# Controller.net
KiCad netlist of a schematic drawn in Altium Designer
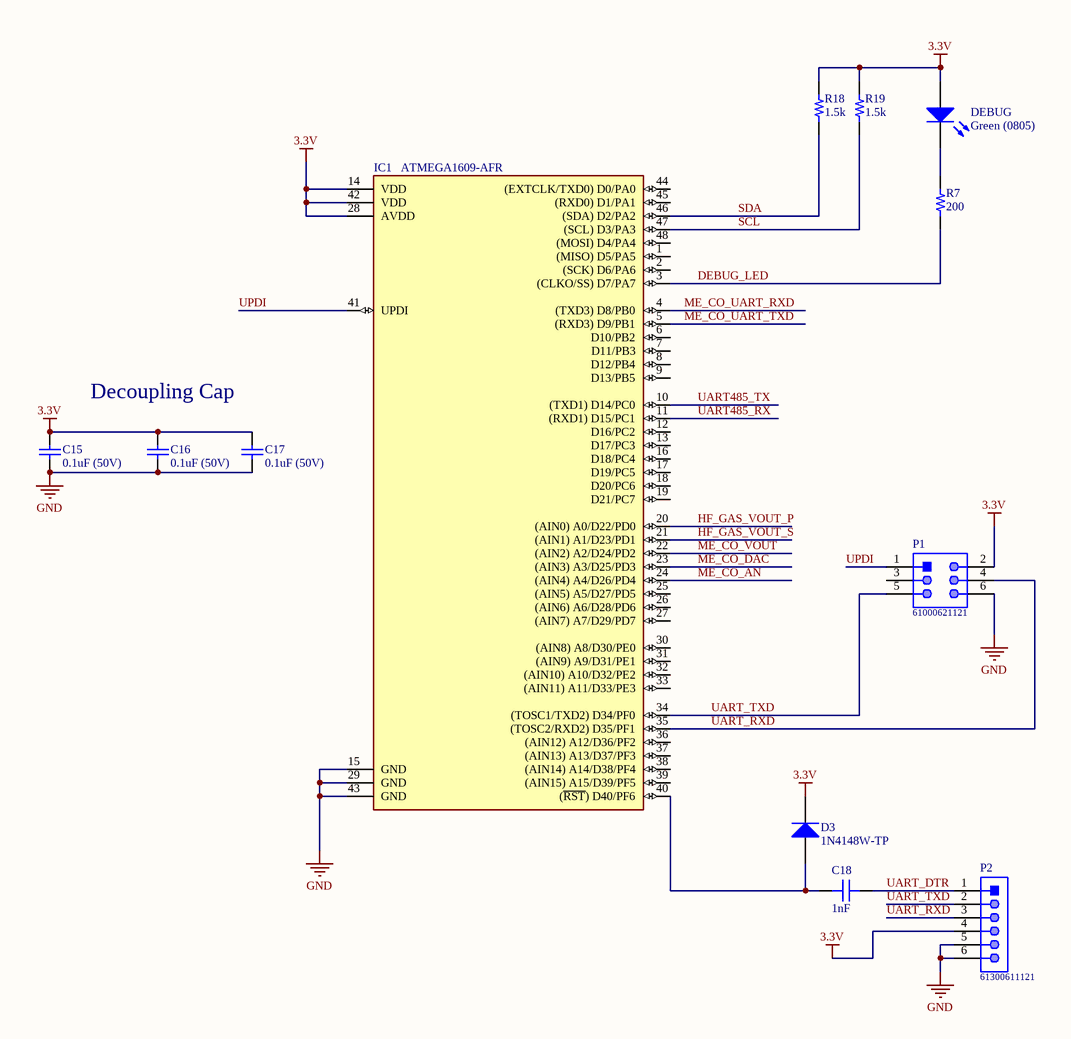
[diagram p0: Controller.SchDoc]

(export (version "E")
  (design (tool "Eeschema 10.0.6"))
  (components
    (comp (ref "C15")
      (value "0.1uF (50V)")
      (footprint "CAPC1608X95X40NL15T15")
      (fields (field (name "PART NUMBER") "VJ0603Y332JXACW1BC") (field (name "MANUFACTURER") "Vitramon"))
      (libsource (lib "Altium Content Vault") (part "CAP"))
    )
    (comp (ref "C16")
      (value "0.1uF (50V)")
      (footprint "CAPC1608X95X40NL15T15")
      (fields (field (name "PART NUMBER") "VJ0603Y332JXACW1BC") (field (name "MANUFACTURER") "Vitramon"))
      (libsource (lib "Altium Content Vault") (part "CAP"))
    )
    (comp (ref "C17")
      (value "0.1uF (50V)")
      (footprint "CAPC1608X95X40NL15T15")
      (fields (field (name "PART NUMBER") "VJ0603Y332JXACW1BC") (field (name "MANUFACTURER") "Vitramon"))
      (libsource (lib "Altium Content Vault") (part "CAP"))
    )
    (comp (ref "C18")
      (value "1nF")
      (footprint "CAP 0603_1608")
      (description "CAP CERAMIC 50V X7R 0603")
      (fields
        (field (name "PART NUMBER") "VJ0603Y332JXACW1BC")
        (field (name "MANUFACTURER") "Vishay Vitramon")
      )
      (libsource (lib "Celestial Altium Library - altium_library") (part "Capacitor"))
    )
    (comp (ref "D3")
      (value "1N4148W-TP")
      (footprint "MCC-SOD123_V")
      (description "High Speed Switching Diode, 400 mW, 150 mA, -65 to 150 degC, 2-Pin SOD123, RoHS, Tape and Reel")
      (fields (field (name "MANUFACTURER") "Micro Commercial Components"))
      (libsource (lib "Altium Content Vault") (part "D-AK-2"))
    )
    (comp (ref "DEBUG")
      (value "Green (0805)")
      (footprint "0805_A")
      (description "SMD mono-color Chip LED, WL-SMCW, Green")
      (fields (field (name "PARTNUMBER") "150080GS75000") (field (name "MANUFACTURER") "Wuerth Elektronik"))
      (libsource (lib "Altium Content Vault") (part "WE-LED_K1A2-2"))
    )
    (comp (ref "IC1")
      (value "ATMEGA1609-AFR")
      (footprint "SamacSys:QFP50P900X900X120-48N")
      (description "Integrated Circuit")
      (fields (field (name "MOUSER PART NUMBER") "579-ATMEGA1609-AFR"))
      (libsource (lib "SamacSys") (part "ATMEGA1609-AFR"))
    )
    (comp (ref "P1")
      (value "61000621121")
      (footprint "61000621121")
      (description "SMT Vertical Pin Header WR-PHD, Pitch 2.54 mm, Dual Row, 6 pins")
      (fields (field (name "MANUFACTURER") "Wurth Elektronik") (field (name "PUBLISHER") "WurthElektronik"))
      (libsource (lib "Altium Content Vault") (part "WE-CN-2P-M-R6"))
    )
    (comp (ref "P2")
      (value "61300611121")
      (footprint "61300611121")
      (description "THT Vertical Pin Header WR-PHD, Pitch 2.54 mm, Single Row, 6 pins")
      (fields (field (name "MANUFACTURER") "Wurth Elektronik") (field (name "PUBLISHER") "WurthElektronik"))
      (libsource (lib "Altium Content Vault") (part "WE-CN-1P-M-R6"))
    )
    (comp (ref "R7")
      (value "200")
      (footprint "RES 0603_1608")
      (description "Resistor")
      (fields (field (name "PART NUMBER") "CRCW060329K4FKEA") (field (name "MANUFACTURER") "Vishay Dale"))
      (libsource (lib "Celestial Altium Library - altium_library") (part "Resistor"))
    )
    (comp (ref "R18")
      (value "1.5k")
      (footprint "RES 0603_1608")
      (description "Resistor")
      (fields (field (name "PART NUMBER") "CRCW060329K4FKEA") (field (name "MANUFACTURER") "Vishay Dale"))
      (libsource (lib "Celestial Altium Library - altium_library") (part "Resistor"))
    )
    (comp (ref "R19")
      (value "1.5k")
      (footprint "RES 0603_1608")
      (description "Resistor")
      (fields (field (name "PART NUMBER") "CRCW060329K4FKEA") (field (name "MANUFACTURER") "Vishay Dale"))
      (libsource (lib "Celestial Altium Library - altium_library") (part "Resistor"))
    )
  )
  (nets
    (net (code "1") (name "/DEBUG_LED") (class "Default")
      (node (ref "IC1") (pin "3") (pinfunction "(CLKO/SS)_D7/PA7_3") (pintype "bidirectional"))
      (node (ref "R7") (pin "1") (pinfunction "1_1") (pintype "passive"))
    )
    (net (code "2") (name "/HF_GAS_VOUT_P") (class "Default")
      (node (ref "IC1") (pin "20") (pinfunction "(AIN0)_A0/D22/PD0_20") (pintype "bidirectional"))
    )
    (net (code "3") (name "/HF_GAS_VOUT_S") (class "Default")
      (node (ref "IC1") (pin "21") (pinfunction "(AIN1)_A1/D23/PD1_21") (pintype "bidirectional"))
    )
    (net (code "4") (name "/ME_CO_AN") (class "Default")
      (node (ref "IC1") (pin "24") (pinfunction "(AIN4)_A4/D26/PD4_24") (pintype "bidirectional"))
    )
    (net (code "5") (name "/ME_CO_DAC") (class "Default")
      (node (ref "IC1") (pin "23") (pinfunction "(AIN3)_A3/D25/PD3_23") (pintype "bidirectional"))
    )
    (net (code "6") (name "/ME_CO_UART_RXD") (class "Default")
      (node (ref "IC1") (pin "4") (pinfunction "(TXD3)_D8/PB0_4") (pintype "bidirectional"))
    )
    (net (code "7") (name "/ME_CO_UART_TXD") (class "Default")
      (node (ref "IC1") (pin "5") (pinfunction "(RXD3)_D9/PB1_5") (pintype "bidirectional"))
    )
    (net (code "8") (name "/ME_CO_VOUT") (class "Default")
      (node (ref "IC1") (pin "22") (pinfunction "(AIN2)_A2/D24/PD2_22") (pintype "bidirectional"))
    )
    (net (code "9") (name "/SCL") (class "Default")
      (node (ref "IC1") (pin "47") (pinfunction "(SCL)_D3/PA3_47") (pintype "bidirectional"))
      (node (ref "R19") (pin "2") (pinfunction "2_2") (pintype "passive"))
    )
    (net (code "10") (name "/SDA") (class "Default")
      (node (ref "IC1") (pin "46") (pinfunction "(SDA)_D2/PA2_46") (pintype "bidirectional"))
      (node (ref "R18") (pin "2") (pinfunction "2_2") (pintype "passive"))
    )
    (net (code "11") (name "/UART485_RX") (class "Default")
      (node (ref "IC1") (pin "11") (pinfunction "(RXD1)_D15/PC1_11") (pintype "bidirectional"))
    )
    (net (code "12") (name "/UART485_TX") (class "Default")
      (node (ref "IC1") (pin "10") (pinfunction "(TXD1)_D14/PC0_10") (pintype "bidirectional"))
    )
    (net (code "13") (name "/UART_DTR") (class "Default")
      (node (ref "C18") (pin "1") (pinfunction "1_1") (pintype "passive"))
      (node (ref "P2") (pin "1") (pinfunction "1_1") (pintype "passive"))
    )
    (net (code "14") (name "/UART_RXD") (class "Default")
      (node (ref "IC1") (pin "35") (pinfunction "(TOSC2/RXD2)_D35/PF1_35") (pintype "bidirectional"))
      (node (ref "P1") (pin "4") (pinfunction "4_4") (pintype "passive"))
      (node (ref "P2") (pin "3") (pinfunction "3_3") (pintype "passive"))
    )
    (net (code "15") (name "/UART_TXD") (class "Default")
      (node (ref "IC1") (pin "34") (pinfunction "(TOSC1/TXD2)_D34/PF0_34") (pintype "bidirectional"))
      (node (ref "P1") (pin "5") (pinfunction "5_5") (pintype "passive"))
      (node (ref "P2") (pin "2") (pinfunction "2_2") (pintype "passive"))
    )
    (net (code "16") (name "/UPDI") (class "Default")
      (node (ref "IC1") (pin "41") (pinfunction "UPDI_41") (pintype "bidirectional"))
      (node (ref "P1") (pin "1") (pinfunction "1_1") (pintype "passive"))
    )
    (net (code "17") (name "3.3V") (class "Default")
      (node (ref "C15") (pin "2") (pinfunction "2_2") (pintype "passive"))
      (node (ref "C16") (pin "2") (pinfunction "2_2") (pintype "passive"))
      (node (ref "C17") (pin "2") (pinfunction "2_2") (pintype "passive"))
      (node (ref "D3") (pin "2") (pinfunction "K_2") (pintype "passive"))
      (node (ref "DEBUG") (pin "2") (pinfunction "A_2") (pintype "passive"))
      (node (ref "IC1") (pin "14") (pinfunction "VDD_14") (pintype "power_in"))
      (node (ref "IC1") (pin "28") (pinfunction "AVDD_28") (pintype "power_in"))
      (node (ref "IC1") (pin "42") (pinfunction "VDD_42") (pintype "power_in"))
      (node (ref "P1") (pin "2") (pinfunction "2_2") (pintype "passive"))
      (node (ref "P2") (pin "4") (pinfunction "4_4") (pintype "passive"))
      (node (ref "R18") (pin "1") (pinfunction "1_1") (pintype "passive"))
      (node (ref "R19") (pin "1") (pinfunction "1_1") (pintype "passive"))
    )
    (net (code "18") (name "GND") (class "Default")
      (node (ref "C15") (pin "1") (pinfunction "1_1") (pintype "passive"))
      (node (ref "C16") (pin "1") (pinfunction "1_1") (pintype "passive"))
      (node (ref "C17") (pin "1") (pinfunction "1_1") (pintype "passive"))
      (node (ref "IC1") (pin "15") (pinfunction "GND_15") (pintype "power_in"))
      (node (ref "IC1") (pin "29") (pinfunction "GND_29") (pintype "power_in"))
      (node (ref "IC1") (pin "43") (pinfunction "GND_43") (pintype "power_in"))
      (node (ref "P1") (pin "6") (pinfunction "6_6") (pintype "passive"))
      (node (ref "P2") (pin "5") (pinfunction "5_5") (pintype "passive"))
      (node (ref "P2") (pin "6") (pinfunction "6_6") (pintype "passive"))
    )
    (net (code "19") (name "Net-(D3-A)") (class "Default")
      (node (ref "C18") (pin "2") (pinfunction "2_2") (pintype "passive"))
      (node (ref "D3") (pin "1") (pinfunction "A_1") (pintype "passive"))
      (node (ref "IC1") (pin "40") (pinfunction "(~{RST})_D40/PF6_40") (pintype "bidirectional"))
    )
    (net (code "20") (name "Net-(DEBUG-K)") (class "Default")
      (node (ref "DEBUG") (pin "1") (pinfunction "K_1") (pintype "passive"))
      (node (ref "R7") (pin "2") (pinfunction "2_2") (pintype "passive"))
    )
    (net (code "21") (name "unconnected-(IC1-(AIN5)_A5{slash}D27{slash}PD5-Pad25)") (class "Default")
      (node (ref "IC1") (pin "25") (pinfunction "(AIN5)_A5/D27/PD5_25") (pintype "bidirectional"))
    )
    (net (code "22") (name "unconnected-(IC1-(AIN6)_A6{slash}D28{slash}PD6-Pad26)") (class "Default")
      (node (ref "IC1") (pin "26") (pinfunction "(AIN6)_A6/D28/PD6_26") (pintype "bidirectional"))
    )
    (net (code "23") (name "unconnected-(IC1-(AIN7)_A7{slash}D29{slash}PD7-Pad27)") (class "Default")
      (node (ref "IC1") (pin "27") (pinfunction "(AIN7)_A7/D29/PD7_27") (pintype "bidirectional"))
    )
    (net (code "24") (name "unconnected-(IC1-(AIN8)_A8{slash}D30{slash}PE0-Pad30)") (class "Default")
      (node (ref "IC1") (pin "30") (pinfunction "(AIN8)_A8/D30/PE0_30") (pintype "bidirectional"))
    )
    (net (code "25") (name "unconnected-(IC1-(AIN9)_A9{slash}D31{slash}PE1-Pad31)") (class "Default")
      (node (ref "IC1") (pin "31") (pinfunction "(AIN9)_A9/D31/PE1_31") (pintype "bidirectional"))
    )
    (net (code "26") (name "unconnected-(IC1-(AIN10)_A10{slash}D32{slash}PE2-Pad32)") (class "Default")
      (node (ref "IC1") (pin "32") (pinfunction "(AIN10)_A10/D32/PE2_32") (pintype "bidirectional"))
    )
    (net (code "27") (name "unconnected-(IC1-(AIN11)_A11{slash}D33{slash}PE3-Pad33)") (class "Default")
      (node (ref "IC1") (pin "33") (pinfunction "(AIN11)_A11/D33/PE3_33") (pintype "bidirectional"))
    )
    (net (code "28") (name "unconnected-(IC1-(AIN12)_A12{slash}D36{slash}PF2-Pad36)") (class "Default")
      (node (ref "IC1") (pin "36") (pinfunction "(AIN12)_A12/D36/PF2_36") (pintype "bidirectional"))
    )
    (net (code "29") (name "unconnected-(IC1-(AIN13)_A13{slash}D37{slash}PF3-Pad37)") (class "Default")
      (node (ref "IC1") (pin "37") (pinfunction "(AIN13)_A13/D37/PF3_37") (pintype "bidirectional"))
    )
    (net (code "30") (name "unconnected-(IC1-(AIN14)_A14{slash}D38{slash}PF4-Pad38)") (class "Default")
      (node (ref "IC1") (pin "38") (pinfunction "(AIN14)_A14/D38/PF4_38") (pintype "bidirectional"))
    )
    (net (code "31") (name "unconnected-(IC1-(AIN15)_A15{slash}D39{slash}PF5-Pad39)") (class "Default")
      (node (ref "IC1") (pin "39") (pinfunction "(AIN15)_A15/D39/PF5_39") (pintype "bidirectional"))
    )
    (net (code "32") (name "unconnected-(IC1-(EXTCLK{slash}TXD0)_D0{slash}PA0-Pad44)") (class "Default")
      (node (ref "IC1") (pin "44") (pinfunction "(EXTCLK/TXD0)_D0/PA0_44") (pintype "bidirectional"))
    )
    (net (code "33") (name "unconnected-(IC1-(MISO)_D5{slash}PA5-Pad1)") (class "Default")
      (node (ref "IC1") (pin "1") (pinfunction "(MISO)_D5/PA5_1") (pintype "bidirectional"))
    )
    (net (code "34") (name "unconnected-(IC1-(MOSI)_D4{slash}PA4-Pad48)") (class "Default")
      (node (ref "IC1") (pin "48") (pinfunction "(MOSI)_D4/PA4_48") (pintype "bidirectional"))
    )
    (net (code "35") (name "unconnected-(IC1-(RXD0)_D1{slash}PA1-Pad45)") (class "Default")
      (node (ref "IC1") (pin "45") (pinfunction "(RXD0)_D1/PA1_45") (pintype "bidirectional"))
    )
    (net (code "36") (name "unconnected-(IC1-(SCK)_D6{slash}PA6-Pad2)") (class "Default")
      (node (ref "IC1") (pin "2") (pinfunction "(SCK)_D6/PA6_2") (pintype "bidirectional"))
    )
    (net (code "37") (name "unconnected-(IC1-D10{slash}PB2-Pad6)") (class "Default")
      (node (ref "IC1") (pin "6") (pinfunction "D10/PB2_6") (pintype "bidirectional"))
    )
    (net (code "38") (name "unconnected-(IC1-D11{slash}PB3-Pad7)") (class "Default")
      (node (ref "IC1") (pin "7") (pinfunction "D11/PB3_7") (pintype "bidirectional"))
    )
    (net (code "39") (name "unconnected-(IC1-D12{slash}PB4-Pad8)") (class "Default")
      (node (ref "IC1") (pin "8") (pinfunction "D12/PB4_8") (pintype "bidirectional"))
    )
    (net (code "40") (name "unconnected-(IC1-D13{slash}PB5-Pad9)") (class "Default")
      (node (ref "IC1") (pin "9") (pinfunction "D13/PB5_9") (pintype "bidirectional"))
    )
    (net (code "41") (name "unconnected-(IC1-D16{slash}PC2-Pad12)") (class "Default")
      (node (ref "IC1") (pin "12") (pinfunction "D16/PC2_12") (pintype "bidirectional"))
    )
    (net (code "42") (name "unconnected-(IC1-D17{slash}PC3-Pad13)") (class "Default")
      (node (ref "IC1") (pin "13") (pinfunction "D17/PC3_13") (pintype "bidirectional"))
    )
    (net (code "43") (name "unconnected-(IC1-D18{slash}PC4-Pad16)") (class "Default")
      (node (ref "IC1") (pin "16") (pinfunction "D18/PC4_16") (pintype "bidirectional"))
    )
    (net (code "44") (name "unconnected-(IC1-D19{slash}PC5-Pad17)") (class "Default")
      (node (ref "IC1") (pin "17") (pinfunction "D19/PC5_17") (pintype "bidirectional"))
    )
    (net (code "45") (name "unconnected-(IC1-D20{slash}PC6-Pad18)") (class "Default")
      (node (ref "IC1") (pin "18") (pinfunction "D20/PC6_18") (pintype "bidirectional"))
    )
    (net (code "46") (name "unconnected-(IC1-D21{slash}PC7-Pad19)") (class "Default")
      (node (ref "IC1") (pin "19") (pinfunction "D21/PC7_19") (pintype "bidirectional"))
    )
    (net (code "47") (name "unconnected-(P1-Pad3)") (class "Default")
      (node (ref "P1") (pin "3") (pinfunction "3_3") (pintype "passive"))
    )
  )
)
